# relays.net
KiCad netlist of a schematic drawn in EAGLE
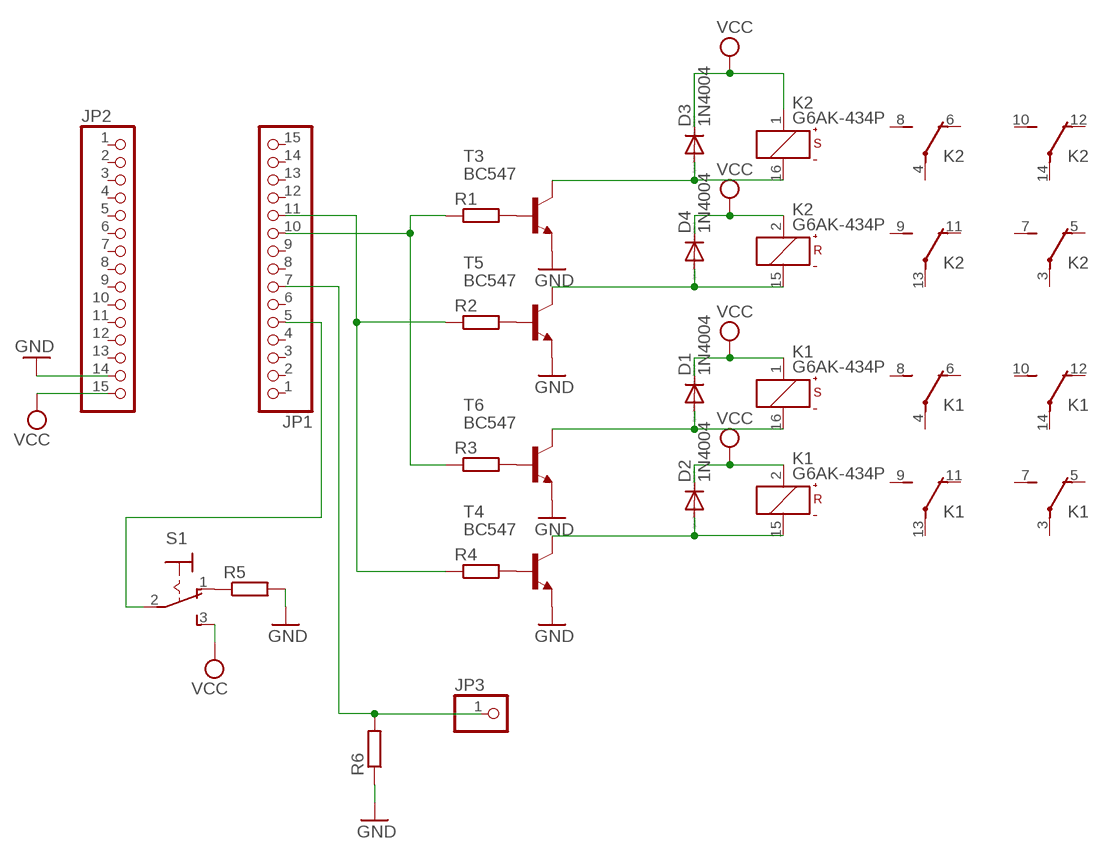
[diagram p0: schematic, sheet 1]

(export (version "E")
  (design (tool "Eeschema 10.0.6"))
  (components
    (comp (ref "D1")
      (value "1N4004")
      (footprint "eagle-import:DO41-10")
      (libsource (lib "eagle-import") (part "1N4004"))
    )
    (comp (ref "D2")
      (value "1N4004")
      (footprint "eagle-import:DO41-10")
      (libsource (lib "eagle-import") (part "1N4004"))
    )
    (comp (ref "D3")
      (value "1N4004")
      (footprint "eagle-import:DO41-10")
      (libsource (lib "eagle-import") (part "1N4004"))
    )
    (comp (ref "D4")
      (value "1N4004")
      (footprint "eagle-import:DO41-10")
      (libsource (lib "eagle-import") (part "1N4004"))
    )
    (comp (ref "JP1")
      (value "PINHD-1X15")
      (footprint "eagle-import:1X15")
      (libsource (lib "eagle-import") (part "PINHD-1X15"))
    )
    (comp (ref "JP2")
      (value "PINHD-1X15")
      (footprint "eagle-import:1X15")
      (libsource (lib "eagle-import") (part "PINHD-1X15"))
    )
    (comp (ref "JP3")
      (value "PINHD-1X1")
      (footprint "eagle-import:1X01")
      (libsource (lib "eagle-import") (part "PINHD-1X1"))
    )
    (comp (ref "K1")
      (value "G6AK-434P")
      (footprint "eagle-import:G6AK-434P")
      (libsource (lib "eagle-import") (part "G6AK-434P"))
    )
    (comp (ref "K2")
      (value "G6AK-434P")
      (footprint "eagle-import:G6AK-434P")
      (libsource (lib "eagle-import") (part "G6AK-434P"))
    )
    (comp (ref "R1")
      (value "R-EU_0207/10")
      (footprint "eagle-import:0207_10")
      (libsource (lib "eagle-import") (part "R-EU_0207/10"))
    )
    (comp (ref "R2")
      (value "R-EU_0207/10")
      (footprint "eagle-import:0207_10")
      (libsource (lib "eagle-import") (part "R-EU_0207/10"))
    )
    (comp (ref "R3")
      (value "R-EU_0207/10")
      (footprint "eagle-import:0207_10")
      (libsource (lib "eagle-import") (part "R-EU_0207/10"))
    )
    (comp (ref "R4")
      (value "R-EU_0207/10")
      (footprint "eagle-import:0207_10")
      (libsource (lib "eagle-import") (part "R-EU_0207/10"))
    )
    (comp (ref "R5")
      (value "R-EU_0207/10")
      (footprint "eagle-import:0207_10")
      (libsource (lib "eagle-import") (part "R-EU_0207/10"))
    )
    (comp (ref "R6")
      (value "R-EU_0207/10")
      (footprint "eagle-import:0207_10")
      (libsource (lib "eagle-import") (part "R-EU_0207/10"))
    )
    (comp (ref "S1")
      (value "320-916")
      (footprint "eagle-import:320-916")
      (libsource (lib "eagle-import") (part "320-916"))
    )
    (comp (ref "T3")
      (value "BC547")
      (footprint "eagle-import:TO92")
      (libsource (lib "eagle-import") (part "BC547"))
    )
    (comp (ref "T4")
      (value "BC547")
      (footprint "eagle-import:TO92")
      (libsource (lib "eagle-import") (part "BC547"))
    )
    (comp (ref "T5")
      (value "BC547")
      (footprint "eagle-import:TO92")
      (libsource (lib "eagle-import") (part "BC547"))
    )
    (comp (ref "T6")
      (value "BC547")
      (footprint "eagle-import:TO92")
      (libsource (lib "eagle-import") (part "BC547"))
    )
  )
  (nets
    (net (code "1") (name "GND") (class "Default")
      (node (ref "JP2") (pin "14") (pinfunction "14_14") (pintype "passive"))
      (node (ref "R5") (pin "2") (pinfunction "2_2") (pintype "passive"))
      (node (ref "R6") (pin "1") (pinfunction "1_1") (pintype "passive"))
      (node (ref "T3") (pin "1") (pinfunction "E_1") (pintype "passive"))
      (node (ref "T4") (pin "1") (pinfunction "E_1") (pintype "passive"))
      (node (ref "T5") (pin "1") (pinfunction "E_1") (pintype "passive"))
      (node (ref "T6") (pin "1") (pinfunction "E_1") (pintype "passive"))
    )
    (net (code "2") (name "Net-(JP1-Pad7)") (class "Default")
      (node (ref "JP1") (pin "7") (pinfunction "7_7") (pintype "passive"))
      (node (ref "JP3") (pin "1") (pinfunction "1_1") (pintype "passive"))
      (node (ref "R6") (pin "2") (pinfunction "2_2") (pintype "passive"))
    )
    (net (code "3") (name "Net-(JP1-Pad10)") (class "Default")
      (node (ref "JP1") (pin "10") (pinfunction "10_10") (pintype "passive"))
      (node (ref "R1") (pin "1") (pinfunction "1_1") (pintype "passive"))
      (node (ref "R3") (pin "1") (pinfunction "1_1") (pintype "passive"))
    )
    (net (code "4") (name "Net-(JP1-Pad11)") (class "Default")
      (node (ref "JP1") (pin "11") (pinfunction "11_11") (pintype "passive"))
      (node (ref "R2") (pin "1") (pinfunction "1_1") (pintype "passive"))
      (node (ref "R4") (pin "1") (pinfunction "1_1") (pintype "passive"))
    )
    (net (code "5") (name "Net-(K1E--)") (class "Default")
      (node (ref "D2") (pin "A") (pinfunction "A_A") (pintype "passive"))
      (node (ref "K1") (pin "15") (pinfunction "-_15") (pintype "passive"))
      (node (ref "T4") (pin "3") (pinfunction "C_3") (pintype "passive"))
    )
    (net (code "6") (name "Net-(K1F--)") (class "Default")
      (node (ref "D1") (pin "A") (pinfunction "A_A") (pintype "passive"))
      (node (ref "K1") (pin "16") (pinfunction "-_16") (pintype "passive"))
      (node (ref "T6") (pin "3") (pinfunction "C_3") (pintype "passive"))
    )
    (net (code "7") (name "Net-(K2E--)") (class "Default")
      (node (ref "D4") (pin "A") (pinfunction "A_A") (pintype "passive"))
      (node (ref "K2") (pin "15") (pinfunction "-_15") (pintype "passive"))
      (node (ref "T5") (pin "3") (pinfunction "C_3") (pintype "passive"))
    )
    (net (code "8") (name "Net-(K2F--)") (class "Default")
      (node (ref "D3") (pin "A") (pinfunction "A_A") (pintype "passive"))
      (node (ref "K2") (pin "16") (pinfunction "-_16") (pintype "passive"))
      (node (ref "T3") (pin "3") (pinfunction "C_3") (pintype "passive"))
    )
    (net (code "9") (name "Net-(S1-O)") (class "Default")
      (node (ref "R5") (pin "1") (pinfunction "1_1") (pintype "passive"))
      (node (ref "S1") (pin "1") (pinfunction "O_1") (pintype "passive"))
    )
    (net (code "10") (name "Net-(S1-P)") (class "Default")
      (node (ref "JP1") (pin "5") (pinfunction "5_5") (pintype "passive"))
      (node (ref "S1") (pin "2") (pinfunction "P_2") (pintype "passive"))
    )
    (net (code "11") (name "Net-(T3-B)") (class "Default")
      (node (ref "R1") (pin "2") (pinfunction "2_2") (pintype "passive"))
      (node (ref "T3") (pin "2") (pinfunction "B_2") (pintype "passive"))
    )
    (net (code "12") (name "Net-(T4-B)") (class "Default")
      (node (ref "R4") (pin "2") (pinfunction "2_2") (pintype "passive"))
      (node (ref "T4") (pin "2") (pinfunction "B_2") (pintype "passive"))
    )
    (net (code "13") (name "Net-(T5-B)") (class "Default")
      (node (ref "R2") (pin "2") (pinfunction "2_2") (pintype "passive"))
      (node (ref "T5") (pin "2") (pinfunction "B_2") (pintype "passive"))
    )
    (net (code "14") (name "Net-(T6-B)") (class "Default")
      (node (ref "R3") (pin "2") (pinfunction "2_2") (pintype "passive"))
      (node (ref "T6") (pin "2") (pinfunction "B_2") (pintype "passive"))
    )
    (net (code "15") (name "VCC") (class "Default")
      (node (ref "D1") (pin "C") (pinfunction "C_C") (pintype "passive"))
      (node (ref "D2") (pin "C") (pinfunction "C_C") (pintype "passive"))
      (node (ref "D3") (pin "C") (pinfunction "C_C") (pintype "passive"))
      (node (ref "D4") (pin "C") (pinfunction "C_C") (pintype "passive"))
      (node (ref "JP2") (pin "15") (pinfunction "15_15") (pintype "passive"))
      (node (ref "K1") (pin "1") (pinfunction "+_1") (pintype "passive"))
      (node (ref "K1") (pin "2") (pinfunction "+_2") (pintype "passive"))
      (node (ref "K2") (pin "1") (pinfunction "+_1") (pintype "passive"))
      (node (ref "K2") (pin "2") (pinfunction "+_2") (pintype "passive"))
      (node (ref "S1") (pin "3") (pinfunction "S_3") (pintype "passive"))
    )
    (net (code "16") (name "unconnected-(JP1-Pad1)") (class "Default")
      (node (ref "JP1") (pin "1") (pinfunction "1_1") (pintype "passive"))
    )
    (net (code "17") (name "unconnected-(JP1-Pad2)") (class "Default")
      (node (ref "JP1") (pin "2") (pinfunction "2_2") (pintype "passive"))
    )
    (net (code "18") (name "unconnected-(JP1-Pad3)") (class "Default")
      (node (ref "JP1") (pin "3") (pinfunction "3_3") (pintype "passive"))
    )
    (net (code "19") (name "unconnected-(JP1-Pad4)") (class "Default")
      (node (ref "JP1") (pin "4") (pinfunction "4_4") (pintype "passive"))
    )
    (net (code "20") (name "unconnected-(JP1-Pad6)") (class "Default")
      (node (ref "JP1") (pin "6") (pinfunction "6_6") (pintype "passive"))
    )
    (net (code "21") (name "unconnected-(JP1-Pad8)") (class "Default")
      (node (ref "JP1") (pin "8") (pinfunction "8_8") (pintype "passive"))
    )
    (net (code "22") (name "unconnected-(JP1-Pad9)") (class "Default")
      (node (ref "JP1") (pin "9") (pinfunction "9_9") (pintype "passive"))
    )
    (net (code "23") (name "unconnected-(JP1-Pad12)") (class "Default")
      (node (ref "JP1") (pin "12") (pinfunction "12_12") (pintype "passive"))
    )
    (net (code "24") (name "unconnected-(JP1-Pad13)") (class "Default")
      (node (ref "JP1") (pin "13") (pinfunction "13_13") (pintype "passive"))
    )
    (net (code "25") (name "unconnected-(JP1-Pad14)") (class "Default")
      (node (ref "JP1") (pin "14") (pinfunction "14_14") (pintype "passive"))
    )
    (net (code "26") (name "unconnected-(JP1-Pad15)") (class "Default")
      (node (ref "JP1") (pin "15") (pinfunction "15_15") (pintype "passive"))
    )
    (net (code "27") (name "unconnected-(JP2-Pad1)") (class "Default")
      (node (ref "JP2") (pin "1") (pinfunction "1_1") (pintype "passive"))
    )
    (net (code "28") (name "unconnected-(JP2-Pad2)") (class "Default")
      (node (ref "JP2") (pin "2") (pinfunction "2_2") (pintype "passive"))
    )
    (net (code "29") (name "unconnected-(JP2-Pad3)") (class "Default")
      (node (ref "JP2") (pin "3") (pinfunction "3_3") (pintype "passive"))
    )
    (net (code "30") (name "unconnected-(JP2-Pad4)") (class "Default")
      (node (ref "JP2") (pin "4") (pinfunction "4_4") (pintype "passive"))
    )
    (net (code "31") (name "unconnected-(JP2-Pad5)") (class "Default")
      (node (ref "JP2") (pin "5") (pinfunction "5_5") (pintype "passive"))
    )
    (net (code "32") (name "unconnected-(JP2-Pad6)") (class "Default")
      (node (ref "JP2") (pin "6") (pinfunction "6_6") (pintype "passive"))
    )
    (net (code "33") (name "unconnected-(JP2-Pad7)") (class "Default")
      (node (ref "JP2") (pin "7") (pinfunction "7_7") (pintype "passive"))
    )
    (net (code "34") (name "unconnected-(JP2-Pad8)") (class "Default")
      (node (ref "JP2") (pin "8") (pinfunction "8_8") (pintype "passive"))
    )
    (net (code "35") (name "unconnected-(JP2-Pad9)") (class "Default")
      (node (ref "JP2") (pin "9") (pinfunction "9_9") (pintype "passive"))
    )
    (net (code "36") (name "unconnected-(JP2-Pad10)") (class "Default")
      (node (ref "JP2") (pin "10") (pinfunction "10_10") (pintype "passive"))
    )
    (net (code "37") (name "unconnected-(JP2-Pad11)") (class "Default")
      (node (ref "JP2") (pin "11") (pinfunction "11_11") (pintype "passive"))
    )
    (net (code "38") (name "unconnected-(JP2-Pad12)") (class "Default")
      (node (ref "JP2") (pin "12") (pinfunction "12_12") (pintype "passive"))
    )
    (net (code "39") (name "unconnected-(JP2-Pad13)") (class "Default")
      (node (ref "JP2") (pin "13") (pinfunction "13_13") (pintype "passive"))
    )
    (net (code "40") (name "unconnected-(K1A-O-Pad6)") (class "Default")
      (node (ref "K1") (pin "6") (pinfunction "O_6") (pintype "passive"))
    )
    (net (code "41") (name "unconnected-(K1A-P-Pad4)") (class "Default")
      (node (ref "K1") (pin "4") (pinfunction "P_4") (pintype "passive"))
    )
    (net (code "42") (name "unconnected-(K1A-S-Pad8)") (class "Default")
      (node (ref "K1") (pin "8") (pinfunction "S_8") (pintype "passive"))
    )
    (net (code "43") (name "unconnected-(K1B-O-Pad11)") (class "Default")
      (node (ref "K1") (pin "11") (pinfunction "O_11") (pintype "passive"))
    )
    (net (code "44") (name "unconnected-(K1B-P-Pad13)") (class "Default")
      (node (ref "K1") (pin "13") (pinfunction "P_13") (pintype "passive"))
    )
    (net (code "45") (name "unconnected-(K1B-S-Pad9)") (class "Default")
      (node (ref "K1") (pin "9") (pinfunction "S_9") (pintype "passive"))
    )
    (net (code "46") (name "unconnected-(K1C-O-Pad12)") (class "Default")
      (node (ref "K1") (pin "12") (pinfunction "O_12") (pintype "passive"))
    )
    (net (code "47") (name "unconnected-(K1C-P-Pad14)") (class "Default")
      (node (ref "K1") (pin "14") (pinfunction "P_14") (pintype "passive"))
    )
    (net (code "48") (name "unconnected-(K1C-S-Pad10)") (class "Default")
      (node (ref "K1") (pin "10") (pinfunction "S_10") (pintype "passive"))
    )
    (net (code "49") (name "unconnected-(K1D-O-Pad5)") (class "Default")
      (node (ref "K1") (pin "5") (pinfunction "O_5") (pintype "passive"))
    )
    (net (code "50") (name "unconnected-(K1D-P-Pad3)") (class "Default")
      (node (ref "K1") (pin "3") (pinfunction "P_3") (pintype "passive"))
    )
    (net (code "51") (name "unconnected-(K1D-S-Pad7)") (class "Default")
      (node (ref "K1") (pin "7") (pinfunction "S_7") (pintype "passive"))
    )
    (net (code "52") (name "unconnected-(K2A-O-Pad6)") (class "Default")
      (node (ref "K2") (pin "6") (pinfunction "O_6") (pintype "passive"))
    )
    (net (code "53") (name "unconnected-(K2A-P-Pad4)") (class "Default")
      (node (ref "K2") (pin "4") (pinfunction "P_4") (pintype "passive"))
    )
    (net (code "54") (name "unconnected-(K2A-S-Pad8)") (class "Default")
      (node (ref "K2") (pin "8") (pinfunction "S_8") (pintype "passive"))
    )
    (net (code "55") (name "unconnected-(K2B-O-Pad11)") (class "Default")
      (node (ref "K2") (pin "11") (pinfunction "O_11") (pintype "passive"))
    )
    (net (code "56") (name "unconnected-(K2B-P-Pad13)") (class "Default")
      (node (ref "K2") (pin "13") (pinfunction "P_13") (pintype "passive"))
    )
    (net (code "57") (name "unconnected-(K2B-S-Pad9)") (class "Default")
      (node (ref "K2") (pin "9") (pinfunction "S_9") (pintype "passive"))
    )
    (net (code "58") (name "unconnected-(K2C-O-Pad12)") (class "Default")
      (node (ref "K2") (pin "12") (pinfunction "O_12") (pintype "passive"))
    )
    (net (code "59") (name "unconnected-(K2C-P-Pad14)") (class "Default")
      (node (ref "K2") (pin "14") (pinfunction "P_14") (pintype "passive"))
    )
    (net (code "60") (name "unconnected-(K2C-S-Pad10)") (class "Default")
      (node (ref "K2") (pin "10") (pinfunction "S_10") (pintype "passive"))
    )
    (net (code "61") (name "unconnected-(K2D-O-Pad5)") (class "Default")
      (node (ref "K2") (pin "5") (pinfunction "O_5") (pintype "passive"))
    )
    (net (code "62") (name "unconnected-(K2D-P-Pad3)") (class "Default")
      (node (ref "K2") (pin "3") (pinfunction "P_3") (pintype "passive"))
    )
    (net (code "63") (name "unconnected-(K2D-S-Pad7)") (class "Default")
      (node (ref "K2") (pin "7") (pinfunction "S_7") (pintype "passive"))
    )
  )
)
